# lora.net
KiCad netlist of a schematic drawn in Altium Designer
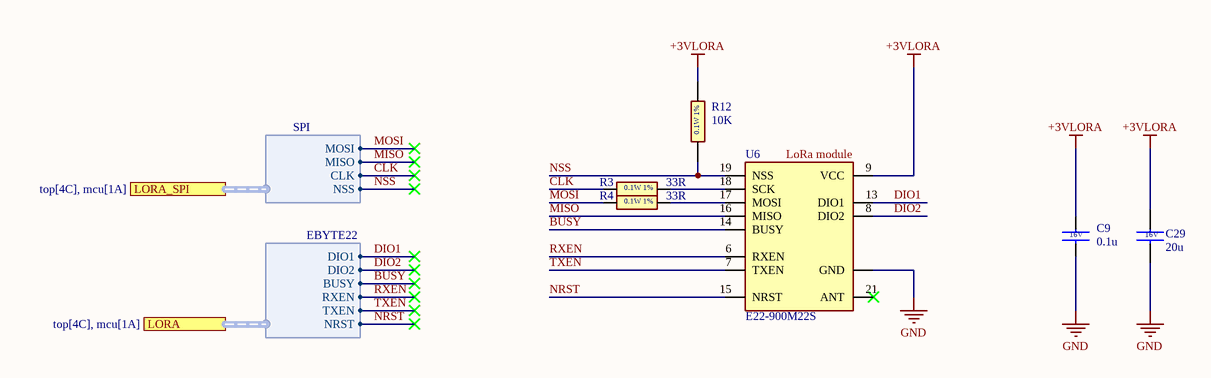
[diagram p0: lora.SchDoc]

(export (version "E")
  (design (tool "Eeschema 10.0.6"))
  (components
    (comp (ref "C9")
      (value "0.1u")
      (footprint "CAPC1608X95N")
      (description "16V 0.1uF XR7 0603 10%")
      (fields
        (field (name "MANUFACTURER_PART_NUMBER") "C0603C104K4RAC-TU")
        (field (name "MOUSER PART NUMBER") "80-C0603C104K4RAC")
      )
      (libsource (lib "bch-lib") (part "ECK+100n16V"))
    )
    (comp (ref "C29")
      (value "20u")
      (footprint "C0603")
      (description "Capacitor")
      (fields
        (field (name "MANUFACTURER_PART_NUMBER") "C0603C200K4HACAUTO")
        (field (name "MOUSER PART NUMBER") "80-C0603C200K4HAUTO")
      )
      (libsource (lib "bch-lib") (part "ECK+20u16V"))
    )
    (comp (ref "R3")
      (value "33R")
      (footprint "RESC1608X55N")
      (description "Resistor 1% 0.1W")
      (fields
        (field (name "MANUFACTURER_PART_NUMBER") "0603WAF330JT5E")
        (field (name "MOUSER PART NUMBER") "303-0603WAF330JT5E")
      )
      (libsource (lib "bch-lib") (part "ER+33R"))
    )
    (comp (ref "R4")
      (value "33R")
      (footprint "RESC1608X55N")
      (description "Resistor 1% 0.1W")
      (fields
        (field (name "MANUFACTURER_PART_NUMBER") "0603WAF330JT5E")
        (field (name "MOUSER PART NUMBER") "303-0603WAF330JT5E")
      )
      (libsource (lib "bch-lib") (part "ER+33R"))
    )
    (comp (ref "R12")
      (value "10K")
      (footprint "RESC1608X50N")
      (description "Resistor 1%, 0.1W")
      (fields
        (field (name "MANUFACTURER_PART_NUMBER") "CRCW060310K0FKEA")
        (field (name "MOUSER PART NUMBER") "71-CRCW0603-10K-E3")
      )
      (libsource (lib "bch-lib") (part "ER+10K"))
    )
    (comp (ref "U6")
      (value "E22-900M22S")
      (footprint "E22-900M22S")
      (description "-147dBm 22.3dBm 7km SPI SMD,14x20mm LoRa Modules ROHS")
      (libsource (lib "bch-lib") (part "EMCU+E22-900M22S"))
    )
  )
  (nets
    (net (code "3") (name "+3VLORA") (class "Default")
      (node (ref "C29") (pin "1") (pinfunction "1_1") (pintype "passive"))
      (node (ref "C9") (pin "1") (pinfunction "1_1") (pintype "passive"))
      (node (ref "R12") (pin "2") (pinfunction "2_2") (pintype "passive"))
      (node (ref "U6") (pin "9") (pinfunction "VCC_9") (pintype "passive"))
    )
    (net (code "4") (name "/BUSY") (class "Default")
      (node (ref "U6") (pin "14") (pinfunction "BUSY_14") (pintype "passive+no_connect"))
    )
    (net (code "5") (name "/CLK") (class "Default")
      (node (ref "R3") (pin "1") (pinfunction "1_1") (pintype "passive+no_connect"))
    )
    (net (code "6") (name "/DIO1") (class "Default")
      (node (ref "U6") (pin "13") (pinfunction "DIO1_13") (pintype "passive+no_connect"))
    )
    (net (code "7") (name "/DIO2") (class "Default")
      (node (ref "U6") (pin "8") (pinfunction "DIO2_8") (pintype "passive+no_connect"))
    )
    (net (code "8") (name "/MISO") (class "Default")
      (node (ref "U6") (pin "16") (pinfunction "MISO_16") (pintype "passive"))
    )
    (net (code "9") (name "/MOSI") (class "Default")
      (node (ref "R4") (pin "1") (pinfunction "1_1") (pintype "passive"))
    )
    (net (code "10") (name "/NRST") (class "Default")
      (node (ref "U6") (pin "15") (pinfunction "NRST_15") (pintype "passive+no_connect"))
    )
    (net (code "11") (name "/NSS") (class "Default")
      (node (ref "R12") (pin "1") (pinfunction "1_1") (pintype "passive"))
      (node (ref "U6") (pin "19") (pinfunction "NSS_19") (pintype "passive"))
    )
    (net (code "12") (name "/RXEN") (class "Default")
      (node (ref "U6") (pin "6") (pinfunction "RXEN_6") (pintype "passive+no_connect"))
    )
    (net (code "13") (name "/TXEN") (class "Default")
      (node (ref "U6") (pin "7") (pinfunction "TXEN_7") (pintype "passive+no_connect"))
    )
    (net (code "16") (name "GND") (class "Default")
      (node (ref "C29") (pin "2") (pinfunction "2_2") (pintype "passive"))
      (node (ref "C9") (pin "2") (pinfunction "2_2") (pintype "passive"))
      (node (ref "U6") (pin "1") (pinfunction "GND_1") (pintype "passive"))
    )
    (net (code "17") (name "Net-(U6-MOSI)") (class "Default")
      (node (ref "R4") (pin "2") (pinfunction "2_2") (pintype "passive"))
      (node (ref "U6") (pin "17") (pinfunction "MOSI_17") (pintype "passive"))
    )
    (net (code "18") (name "Net-(U6-SCK)") (class "Default")
      (node (ref "R3") (pin "2") (pinfunction "2_2") (pintype "passive"))
      (node (ref "U6") (pin "18") (pinfunction "SCK_18") (pintype "passive"))
    )
    (net (code "19") (name "unconnected-(U6-ANT-Pad21)") (class "Default")
      (node (ref "U6") (pin "21") (pinfunction "ANT_21") (pintype "passive+no_connect"))
    )
  )
)
